# TX_LPF_Add_on.net
KiCad netlist of a schematic drawn in Altium Designer
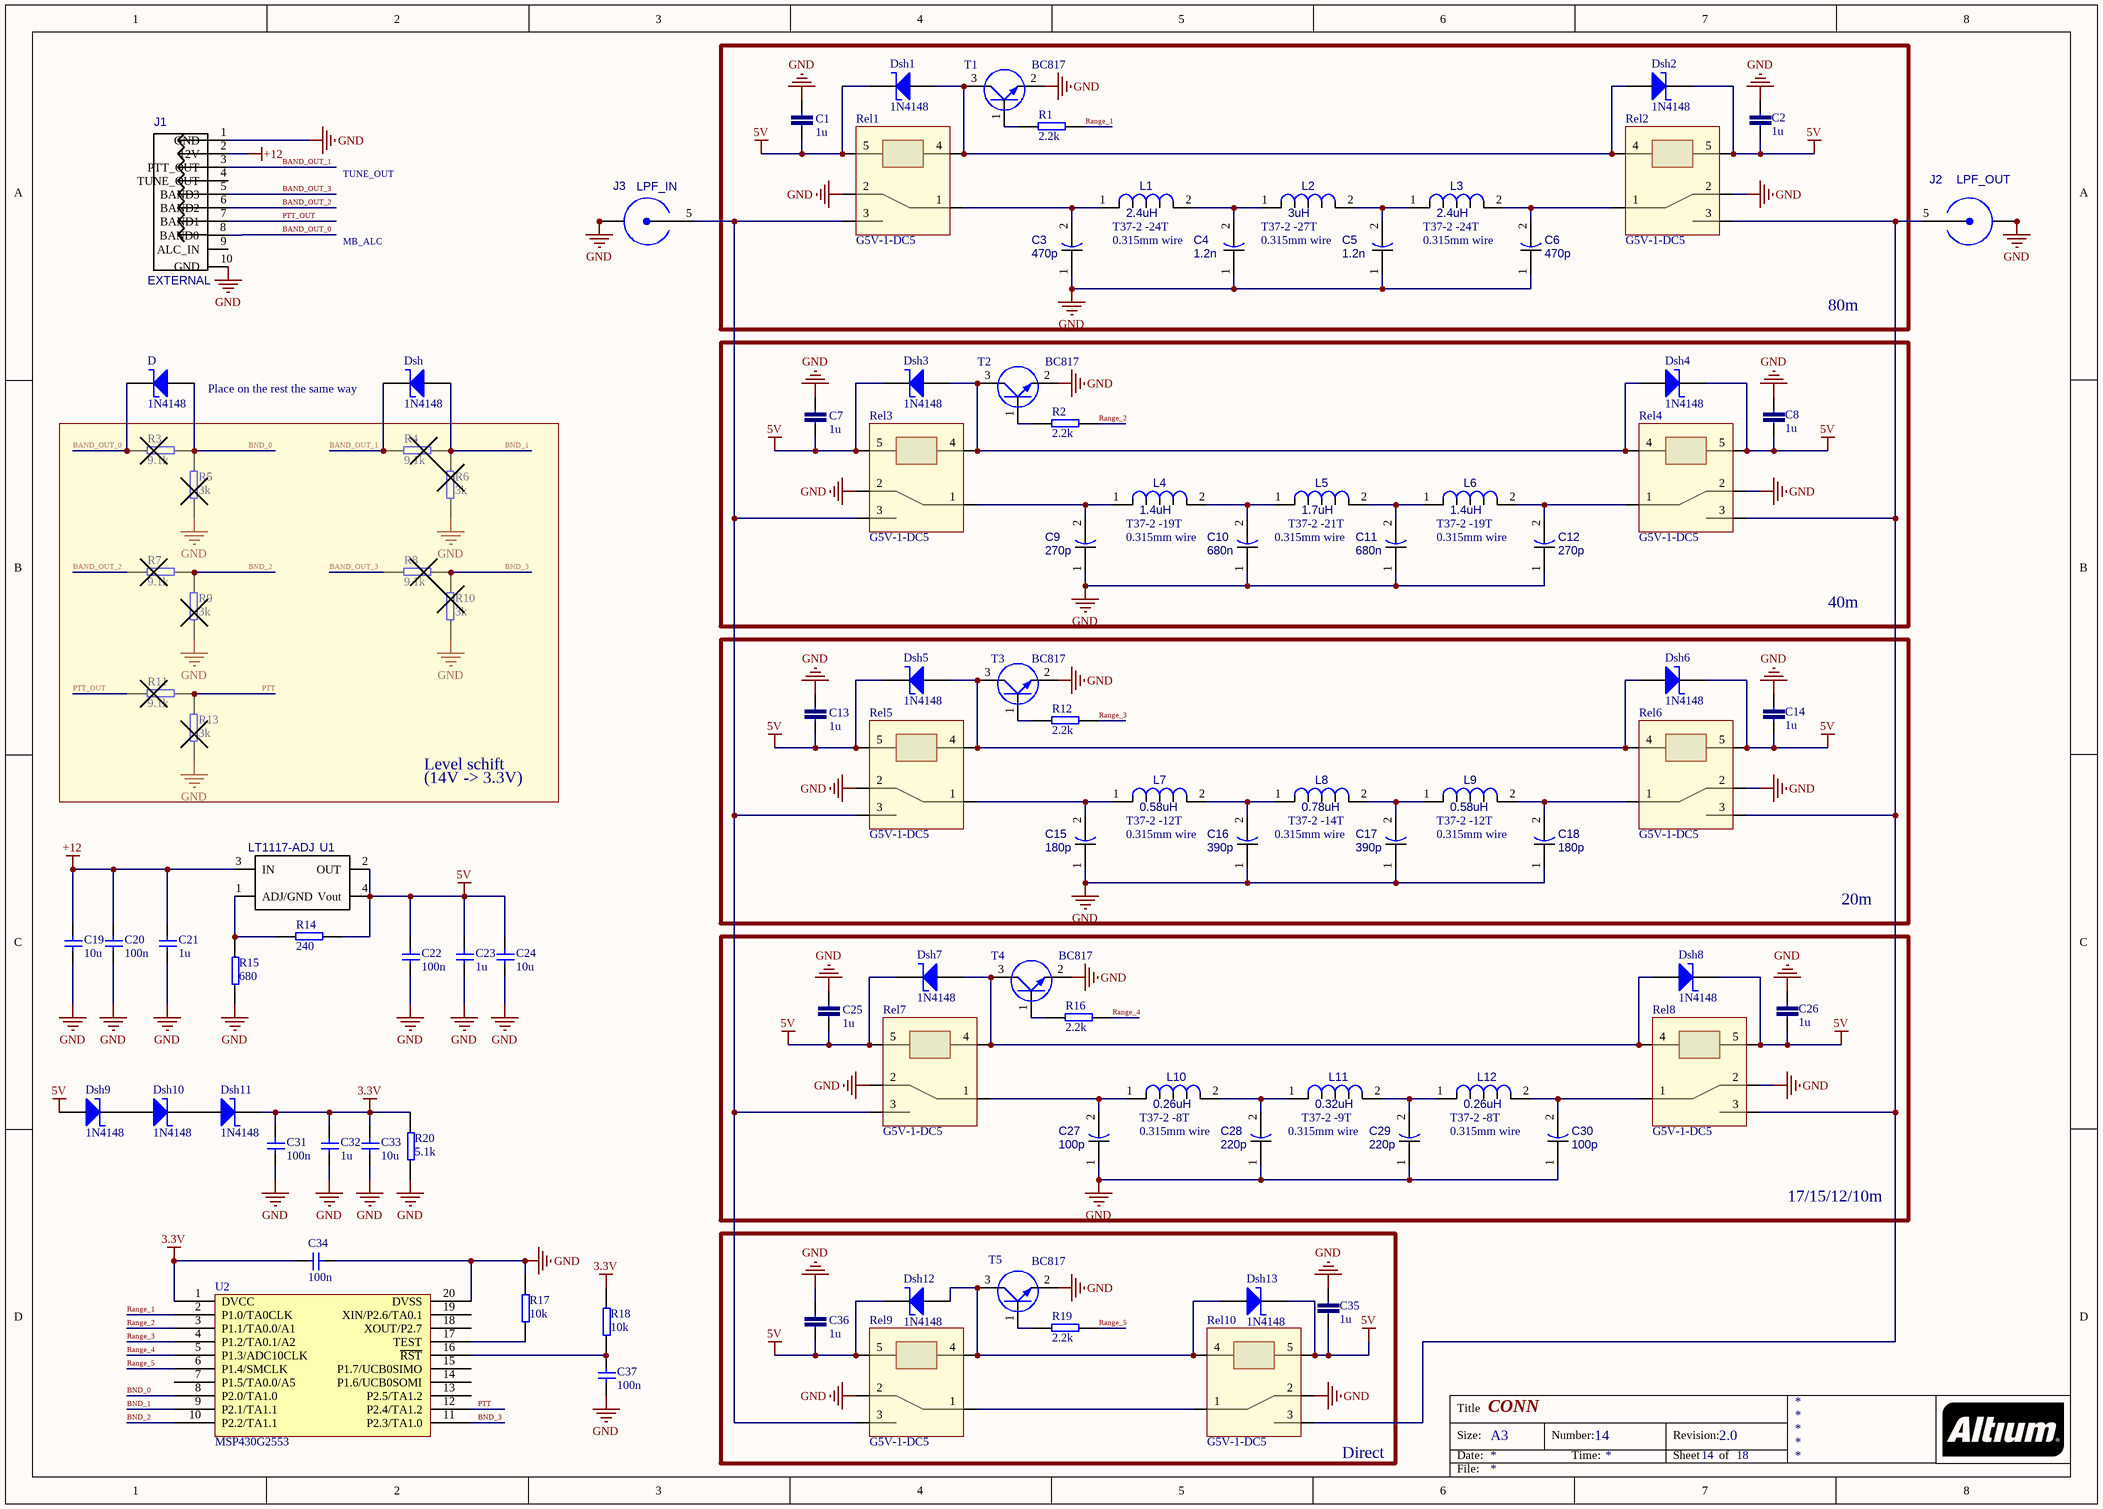
[diagram p0: TX_LPF_Add_on.SchDoc]

(export (version "E")
  (design (tool "Eeschema 10.0.6"))
  (components
    (comp (ref "C1")
      (value "1u")
      (footprint "0805S")
      (description "Capacitor")
      (libsource (lib "XXYZZB_1") (part "C-EUC0805"))
    )
    (comp (ref "C2")
      (value "1u")
      (footprint "0805S")
      (description "Capacitor")
      (libsource (lib "") (part "C-EUC0805_1"))
    )
    (comp (ref "C3")
      (value "470p")
      (footprint "CAP_5mm")
      (description "CAP_1206")
      (fields (field (name "Comment") "CAP_5mm"))
      (libsource (lib "RF-UNIT") (part "CAP_5mm"))
    )
    (comp (ref "C4")
      (value "1.2n")
      (footprint "CAP_5mm")
      (description "CAP_1206")
      (fields (field (name "Comment") "CAP_5mm"))
      (libsource (lib "RF-UNIT") (part "CAP_5mm"))
    )
    (comp (ref "C5")
      (value "1.2n")
      (footprint "CAP_5mm")
      (description "CAP_1206")
      (fields (field (name "Comment") "CAP_5mm"))
      (libsource (lib "RF-UNIT") (part "CAP_5mm"))
    )
    (comp (ref "C6")
      (value "470p")
      (footprint "CAP_5mm")
      (description "CAP_1206")
      (fields (field (name "Comment") "CAP_5mm"))
      (libsource (lib "RF-UNIT") (part "CAP_5mm"))
    )
    (comp (ref "C7")
      (value "1u")
      (footprint "0805S")
      (description "Capacitor")
      (libsource (lib "XXYZZB_1") (part "C-EUC0805"))
    )
    (comp (ref "C8")
      (value "1u")
      (footprint "0805S")
      (description "Capacitor")
      (libsource (lib "") (part "C-EUC0805_1"))
    )
    (comp (ref "C9")
      (value "270p")
      (footprint "CAP_5mm")
      (description "CAP_1206")
      (fields (field (name "Comment") "CAP_5mm"))
      (libsource (lib "RF-UNIT") (part "CAP_5mm"))
    )
    (comp (ref "C10")
      (value "680n")
      (footprint "CAP_5mm")
      (description "CAP_1206")
      (fields (field (name "Comment") "CAP_5mm"))
      (libsource (lib "RF-UNIT") (part "CAP_5mm"))
    )
    (comp (ref "C11")
      (value "680n")
      (footprint "CAP_5mm")
      (description "CAP_1206")
      (fields (field (name "Comment") "CAP_5mm"))
      (libsource (lib "RF-UNIT") (part "CAP_5mm"))
    )
    (comp (ref "C12")
      (value "270p")
      (footprint "CAP_5mm")
      (description "CAP_1206")
      (fields (field (name "Comment") "CAP_5mm"))
      (libsource (lib "RF-UNIT") (part "CAP_5mm"))
    )
    (comp (ref "C13")
      (value "1u")
      (footprint "0805S")
      (description "Capacitor")
      (libsource (lib "XXYZZB_1") (part "C-EUC0805"))
    )
    (comp (ref "C14")
      (value "1u")
      (footprint "0805S")
      (description "Capacitor")
      (libsource (lib "") (part "C-EUC0805_1"))
    )
    (comp (ref "C15")
      (value "180p")
      (footprint "CAP_5mm")
      (description "CAP_1206")
      (fields (field (name "Comment") "CAP_5mm"))
      (libsource (lib "RF-UNIT") (part "CAP_5mm"))
    )
    (comp (ref "C16")
      (value "390p")
      (footprint "CAP_5mm")
      (description "CAP_1206")
      (fields (field (name "Comment") "CAP_5mm"))
      (libsource (lib "RF-UNIT") (part "CAP_5mm"))
    )
    (comp (ref "C17")
      (value "390p")
      (footprint "CAP_5mm")
      (description "CAP_1206")
      (fields (field (name "Comment") "CAP_5mm"))
      (libsource (lib "RF-UNIT") (part "CAP_5mm"))
    )
    (comp (ref "C18")
      (value "180p")
      (footprint "CAP_5mm")
      (description "CAP_1206")
      (fields (field (name "Comment") "CAP_5mm"))
      (libsource (lib "RF-UNIT") (part "CAP_5mm"))
    )
    (comp (ref "C19")
      (value "10u")
      (footprint "CAP_1206")
      (description "Capacitor")
      (fields (field (name "Comment") "C0805"))
      (libsource (lib "Ivan DXP SCH LIB") (part "C0805"))
    )
    (comp (ref "C20")
      (value "100n")
      (footprint "0805S")
      (description "Capacitor")
      (fields (field (name "Comment") "C0805"))
      (libsource (lib "Ivan DXP SCH LIB") (part "C0805"))
    )
    (comp (ref "C21")
      (value "1u")
      (footprint "0805S")
      (description "Capacitor")
      (fields (field (name "Comment") "C0805"))
      (libsource (lib "Ivan DXP SCH LIB") (part "C0805"))
    )
    (comp (ref "C22")
      (value "100n")
      (footprint "0805S")
      (description "Capacitor")
      (fields (field (name "Comment") "C0805"))
      (libsource (lib "Ivan DXP SCH LIB") (part "C0805"))
    )
    (comp (ref "C23")
      (value "1u")
      (footprint "0805S")
      (description "Capacitor")
      (fields (field (name "Comment") "C0805"))
      (libsource (lib "Ivan DXP SCH LIB") (part "C0805"))
    )
    (comp (ref "C24")
      (value "10u")
      (footprint "CAP_1206")
      (description "Capacitor")
      (fields (field (name "Comment") "C0805"))
      (libsource (lib "Ivan DXP SCH LIB") (part "C0805"))
    )
    (comp (ref "C25")
      (value "1u")
      (footprint "0805S")
      (description "Capacitor")
      (libsource (lib "XXYZZB_1") (part "C-EUC0805"))
    )
    (comp (ref "C26")
      (value "1u")
      (footprint "0805S")
      (description "Capacitor")
      (libsource (lib "") (part "C-EUC0805_1"))
    )
    (comp (ref "C27")
      (value "100p")
      (footprint "CAP_5mm")
      (description "CAP_1206")
      (fields (field (name "Comment") "CAP_5mm"))
      (libsource (lib "RF-UNIT") (part "CAP_5mm"))
    )
    (comp (ref "C28")
      (value "220p")
      (footprint "CAP_5mm")
      (description "CAP_1206")
      (fields (field (name "Comment") "CAP_5mm"))
      (libsource (lib "RF-UNIT") (part "CAP_5mm"))
    )
    (comp (ref "C29")
      (value "220p")
      (footprint "CAP_5mm")
      (description "CAP_1206")
      (fields (field (name "Comment") "CAP_5mm"))
      (libsource (lib "RF-UNIT") (part "CAP_5mm"))
    )
    (comp (ref "C30")
      (value "100p")
      (footprint "CAP_5mm")
      (description "CAP_1206")
      (fields (field (name "Comment") "CAP_5mm"))
      (libsource (lib "RF-UNIT") (part "CAP_5mm"))
    )
    (comp (ref "C31")
      (value "100n")
      (footprint "0805S")
      (description "Capacitor")
      (fields (field (name "Comment") "C0805"))
      (libsource (lib "Ivan DXP SCH LIB") (part "C0805"))
    )
    (comp (ref "C32")
      (value "1u")
      (footprint "0805S")
      (description "Capacitor")
      (fields (field (name "Comment") "C0805"))
      (libsource (lib "Ivan DXP SCH LIB") (part "C0805"))
    )
    (comp (ref "C33")
      (value "10u")
      (footprint "CAP_1206")
      (description "Capacitor")
      (fields (field (name "Comment") "C0805"))
      (libsource (lib "Ivan DXP SCH LIB") (part "C0805"))
    )
    (comp (ref "C34")
      (value "100n")
      (footprint "0805S")
      (description "Capacitor")
      (fields (field (name "Comment") "C0805"))
      (libsource (lib "Ivan DXP SCH LIB") (part "C0805"))
    )
    (comp (ref "C35")
      (value "1u")
      (footprint "0805S")
      (description "Capacitor")
      (libsource (lib "") (part "C-EUC0805_1"))
    )
    (comp (ref "C36")
      (value "1u")
      (footprint "0805S")
      (description "Capacitor")
      (libsource (lib "XXYZZB_1") (part "C-EUC0805"))
    )
    (comp (ref "C37")
      (value "100n")
      (footprint "0805S")
      (description "Capacitor")
      (fields (field (name "Comment") "C0805"))
      (libsource (lib "Ivan DXP SCH LIB") (part "C0805"))
    )
    (comp (ref "D")
      (value "1N4148")
      (footprint "1N4148 (1005)")
      (description "Diode Shottky")
      (fields (field (name "Comment") "DIODE_Shottky_Micr.M"))
      (libsource (lib "Ivan DXP SCH LIB") (part "DIODE_Shottky_Micr.M"))
    )
    (comp (ref "Dsh")
      (value "1N4148")
      (footprint "1N4148 (1005)")
      (description "Diode Shottky")
      (fields (field (name "Comment") "DIODE_Shottky_Micr.M"))
      (libsource (lib "Ivan DXP SCH LIB") (part "DIODE_Shottky_Micr.M"))
    )
    (comp (ref "Dsh1")
      (value "1N4148")
      (footprint "1N4148 (1005)")
      (description "Diode Shottky")
      (fields (field (name "Comment") "DIODE_Shottky_Micr.M"))
      (libsource (lib "Ivan DXP SCH LIB") (part "DIODE_Shottky_Micr.M"))
    )
    (comp (ref "Dsh2")
      (value "1N4148")
      (footprint "1N4148 (1005)")
      (description "Diode Shottky")
      (fields (field (name "Comment") "DIODE_Shottky_Micr.M"))
      (libsource (lib "Ivan DXP SCH LIB") (part "DIODE_Shottky_Micr.M"))
    )
    (comp (ref "Dsh3")
      (value "1N4148")
      (footprint "1N4148 (1005)")
      (description "Diode Shottky")
      (fields (field (name "Comment") "DIODE_Shottky_Micr.M"))
      (libsource (lib "Ivan DXP SCH LIB") (part "DIODE_Shottky_Micr.M"))
    )
    (comp (ref "Dsh4")
      (value "1N4148")
      (footprint "1N4148 (1005)")
      (description "Diode Shottky")
      (fields (field (name "Comment") "DIODE_Shottky_Micr.M"))
      (libsource (lib "Ivan DXP SCH LIB") (part "DIODE_Shottky_Micr.M"))
    )
    (comp (ref "Dsh5")
      (value "1N4148")
      (footprint "1N4148 (1005)")
      (description "Diode Shottky")
      (fields (field (name "Comment") "DIODE_Shottky_Micr.M"))
      (libsource (lib "Ivan DXP SCH LIB") (part "DIODE_Shottky_Micr.M"))
    )
    (comp (ref "Dsh6")
      (value "1N4148")
      (footprint "1N4148 (1005)")
      (description "Diode Shottky")
      (fields (field (name "Comment") "DIODE_Shottky_Micr.M"))
      (libsource (lib "Ivan DXP SCH LIB") (part "DIODE_Shottky_Micr.M"))
    )
    (comp (ref "Dsh7")
      (value "1N4148")
      (footprint "1N4148 (1005)")
      (description "Diode Shottky")
      (fields (field (name "Comment") "DIODE_Shottky_Micr.M"))
      (libsource (lib "Ivan DXP SCH LIB") (part "DIODE_Shottky_Micr.M"))
    )
    (comp (ref "Dsh8")
      (value "1N4148")
      (footprint "1N4148 (1005)")
      (description "Diode Shottky")
      (fields (field (name "Comment") "DIODE_Shottky_Micr.M"))
      (libsource (lib "Ivan DXP SCH LIB") (part "DIODE_Shottky_Micr.M"))
    )
    (comp (ref "Dsh9")
      (value "1N4148")
      (footprint "1N4148 (1005)")
      (description "Diode Shottky")
      (fields (field (name "Comment") "DIODE_Shottky_Micr.M"))
      (libsource (lib "Ivan DXP SCH LIB") (part "DIODE_Shottky_Micr.M"))
    )
    (comp (ref "Dsh10")
      (value "1N4148")
      (footprint "1N4148 (1005)")
      (description "Diode Shottky")
      (fields (field (name "Comment") "DIODE_Shottky_Micr.M"))
      (libsource (lib "Ivan DXP SCH LIB") (part "DIODE_Shottky_Micr.M"))
    )
    (comp (ref "Dsh11")
      (value "1N4148")
      (footprint "1N4148 (1005)")
      (description "Diode Shottky")
      (fields (field (name "Comment") "DIODE_Shottky_Micr.M"))
      (libsource (lib "Ivan DXP SCH LIB") (part "DIODE_Shottky_Micr.M"))
    )
    (comp (ref "Dsh12")
      (value "1N4148")
      (footprint "1N4148 (1005)")
      (description "Diode Shottky")
      (fields (field (name "Comment") "DIODE_Shottky_Micr.M"))
      (libsource (lib "Ivan DXP SCH LIB") (part "DIODE_Shottky_Micr.M"))
    )
    (comp (ref "Dsh13")
      (value "1N4148")
      (footprint "1N4148 (1005)")
      (description "Diode Shottky")
      (fields (field (name "Comment") "DIODE_Shottky_Micr.M"))
      (libsource (lib "Ivan DXP SCH LIB") (part "DIODE_Shottky_Micr.M"))
    )
    (comp (ref "J1")
      (value "EXTERNAL")
      (footprint "90131-0126")
      (description "2*5 PIN")
      (libsource (lib "RF-UNIT") (part "90131-0126"))
    )
    (comp (ref "J2")
      (value "LPF_OUT")
      (footprint "31-5431")
      (description "SMA")
      (fields (field (name "Comment") "Output"))
      (libsource (lib "RF-UNIT_1") (part "31-5431"))
    )
    (comp (ref "J3")
      (value "LPF_IN")
      (footprint "31-5431")
      (description "SMA")
      (fields (field (name "Comment") "Input"))
      (libsource (lib "RF-UNIT_1") (part "31-5431"))
    )
    (comp (ref "L1")
      (value "2.4uH")
      (footprint "IND_T37-2")
      (description "IND_T37-2")
      (libsource (lib "RF-UNIT") (part "IND_T37-2"))
    )
    (comp (ref "L2")
      (value "3uH")
      (footprint "IND_T37-2")
      (description "IND_T37-2")
      (libsource (lib "RF-UNIT") (part "IND_T37-2"))
    )
    (comp (ref "L3")
      (value "2.4uH")
      (footprint "IND_T37-2")
      (description "IND_T37-2")
      (libsource (lib "RF-UNIT") (part "IND_T37-2"))
    )
    (comp (ref "L4")
      (value "1.4uH")
      (footprint "IND_T37-2")
      (description "IND_T37-2")
      (libsource (lib "RF-UNIT") (part "IND_T37-2"))
    )
    (comp (ref "L5")
      (value "1.7uH")
      (footprint "IND_T37-2")
      (description "IND_T37-2")
      (libsource (lib "RF-UNIT") (part "IND_T37-2"))
    )
    (comp (ref "L6")
      (value "1.4uH")
      (footprint "IND_T37-2")
      (description "IND_T37-2")
      (libsource (lib "RF-UNIT") (part "IND_T37-2"))
    )
    (comp (ref "L7")
      (value "0.58uH")
      (footprint "IND_T37-2")
      (description "IND_T37-2")
      (libsource (lib "RF-UNIT") (part "IND_T37-2"))
    )
    (comp (ref "L8")
      (value "0.78uH")
      (footprint "IND_T37-2")
      (description "IND_T37-2")
      (libsource (lib "RF-UNIT") (part "IND_T37-2"))
    )
    (comp (ref "L9")
      (value "0.58uH")
      (footprint "IND_T37-2")
      (description "IND_T37-2")
      (libsource (lib "RF-UNIT") (part "IND_T37-2"))
    )
    (comp (ref "L10")
      (value "0.26uH")
      (footprint "IND_T37-2")
      (description "IND_T37-2")
      (libsource (lib "RF-UNIT") (part "IND_T37-2"))
    )
    (comp (ref "L11")
      (value "0.32uH")
      (footprint "IND_T37-2")
      (description "IND_T37-2")
      (libsource (lib "RF-UNIT") (part "IND_T37-2"))
    )
    (comp (ref "L12")
      (value "0.26uH")
      (footprint "IND_T37-2")
      (description "IND_T37-2")
      (libsource (lib "RF-UNIT") (part "IND_T37-2"))
    )
    (comp (ref "R1")
      (value "2.2k")
      (footprint "0805S")
      (description "Resistor")
      (libsource (lib "Ivan DXP SCH LIB") (part "R0805"))
    )
    (comp (ref "R2")
      (value "2.2k")
      (footprint "0805S")
      (description "Resistor")
      (libsource (lib "Ivan DXP SCH LIB") (part "R0805"))
    )
    (comp (ref "R3")
      (value "9.1k")
      (footprint "0805S")
      (description "Resistor")
      (fields (field (name "Comment") "R0805"))
      (libsource (lib "Ivan DXP SCH LIB") (part "R0805"))
    )
    (comp (ref "R4")
      (value "9.1k")
      (footprint "0805S")
      (description "Resistor")
      (fields (field (name "Comment") "R0805"))
      (libsource (lib "Ivan DXP SCH LIB") (part "R0805"))
    )
    (comp (ref "R5")
      (value "3k")
      (footprint "0805S")
      (description "Resistor")
      (fields (field (name "Comment") "R0805"))
      (libsource (lib "") (part "R0805_1"))
    )
    (comp (ref "R6")
      (value "3k")
      (footprint "0805S")
      (description "Resistor")
      (fields (field (name "Comment") "R0805"))
      (libsource (lib "") (part "R0805_1"))
    )
    (comp (ref "R7")
      (value "9.1k")
      (footprint "0805S")
      (description "Resistor")
      (fields (field (name "Comment") "R0805"))
      (libsource (lib "Ivan DXP SCH LIB") (part "R0805"))
    )
    (comp (ref "R8")
      (value "9.1k")
      (footprint "0805S")
      (description "Resistor")
      (fields (field (name "Comment") "R0805"))
      (libsource (lib "Ivan DXP SCH LIB") (part "R0805"))
    )
    (comp (ref "R9")
      (value "3k")
      (footprint "0805S")
      (description "Resistor")
      (fields (field (name "Comment") "R0805"))
      (libsource (lib "") (part "R0805_1"))
    )
    (comp (ref "R10")
      (value "3k")
      (footprint "0805S")
      (description "Resistor")
      (fields (field (name "Comment") "R0805"))
      (libsource (lib "") (part "R0805_1"))
    )
    (comp (ref "R11")
      (value "9.1k")
      (footprint "0805S")
      (description "Resistor")
      (fields (field (name "Comment") "R0805"))
      (libsource (lib "Ivan DXP SCH LIB") (part "R0805"))
    )
    (comp (ref "R12")
      (value "2.2k")
      (footprint "0805S")
      (description "Resistor")
      (libsource (lib "Ivan DXP SCH LIB") (part "R0805"))
    )
    (comp (ref "R13")
      (value "3k")
      (footprint "0805S")
      (description "Resistor")
      (fields (field (name "Comment") "R0805"))
      (libsource (lib "") (part "R0805_1"))
    )
    (comp (ref "R14")
      (value "240")
      (footprint "0805S")
      (description "Resistor")
      (fields (field (name "Comment") "R0805"))
      (libsource (lib "Ivan DXP SCH LIB") (part "R0805"))
    )
    (comp (ref "R15")
      (value "680")
      (footprint "0805S")
      (description "Resistor")
      (fields (field (name "Comment") "R0805"))
      (libsource (lib "") (part "R0805_2"))
    )
    (comp (ref "R16")
      (value "2.2k")
      (footprint "0805S")
      (description "Resistor")
      (libsource (lib "Ivan DXP SCH LIB") (part "R0805"))
    )
    (comp (ref "R17")
      (value "10k")
      (footprint "0805S")
      (description "Resistor")
      (fields (field (name "Comment") "R0805"))
      (libsource (lib "") (part "R0805_2"))
    )
    (comp (ref "R18")
      (value "10k")
      (footprint "0805S")
      (description "Resistor")
      (fields (field (name "Comment") "R0805"))
      (libsource (lib "") (part "R0805_2"))
    )
    (comp (ref "R19")
      (value "2.2k")
      (footprint "0805S")
      (description "Resistor")
      (libsource (lib "Ivan DXP SCH LIB") (part "R0805"))
    )
    (comp (ref "R20")
      (value "5.1k")
      (footprint "0805S")
      (description "Resistor")
      (fields (field (name "Comment") "R0805"))
      (libsource (lib "") (part "R0805_2"))
    )
    (comp (ref "Rel1") (value "G5V-1-DC5") (footprint "G5V-1") (libsource (lib "") (part "G5V-1-DC5_1")))
    (comp (ref "Rel2")
      (value "G5V-1-DC5")
      (footprint "G5V-1")
      (libsource (lib "IC_Texas_Instruments_ADS805E_eec") (part "G5V-1-DC5"))
    )
    (comp (ref "Rel3") (value "G5V-1-DC5") (footprint "G5V-1") (libsource (lib "") (part "G5V-1-DC5_1")))
    (comp (ref "Rel4")
      (value "G5V-1-DC5")
      (footprint "G5V-1")
      (libsource (lib "IC_Texas_Instruments_ADS805E_eec") (part "G5V-1-DC5"))
    )
    (comp (ref "Rel5") (value "G5V-1-DC5") (footprint "G5V-1") (libsource (lib "") (part "G5V-1-DC5_1")))
    (comp (ref "Rel6")
      (value "G5V-1-DC5")
      (footprint "G5V-1")
      (libsource (lib "IC_Texas_Instruments_ADS805E_eec") (part "G5V-1-DC5"))
    )
    (comp (ref "Rel7") (value "G5V-1-DC5") (footprint "G5V-1") (libsource (lib "") (part "G5V-1-DC5_1")))
    (comp (ref "Rel8")
      (value "G5V-1-DC5")
      (footprint "G5V-1")
      (libsource (lib "IC_Texas_Instruments_ADS805E_eec") (part "G5V-1-DC5"))
    )
    (comp (ref "Rel9") (value "G5V-1-DC5") (footprint "G5V-1") (libsource (lib "") (part "G5V-1-DC5_1")))
    (comp (ref "Rel10")
      (value "G5V-1-DC5")
      (footprint "G5V-1")
      (libsource (lib "IC_Texas_Instruments_ADS805E_eec") (part "G5V-1-DC5"))
    )
    (comp (ref "T1")
      (value "BC817")
      (footprint "SOT-23")
      (description "Bipol. Transistor")
      (fields (field (name "Comment") "NPN"))
      (libsource (lib "Ivan DXP SCH LIB") (part "NPN"))
    )
    (comp (ref "T2")
      (value "BC817")
      (footprint "SOT-23")
      (description "Bipol. Transistor")
      (fields (field (name "Comment") "NPN"))
      (libsource (lib "Ivan DXP SCH LIB") (part "NPN"))
    )
    (comp (ref "T3")
      (value "BC817")
      (footprint "SOT-23")
      (description "Bipol. Transistor")
      (fields (field (name "Comment") "NPN"))
      (libsource (lib "Ivan DXP SCH LIB") (part "NPN"))
    )
    (comp (ref "T4")
      (value "BC817")
      (footprint "SOT-23")
      (description "Bipol. Transistor")
      (fields (field (name "Comment") "NPN"))
      (libsource (lib "Ivan DXP SCH LIB") (part "NPN"))
    )
    (comp (ref "T5")
      (value "BC817")
      (footprint "SOT-23")
      (description "Bipol. Transistor")
      (fields (field (name "Comment") "NPN"))
      (libsource (lib "Ivan DXP SCH LIB") (part "NPN"))
    )
    (comp (ref "U1")
      (value "LT1117-ADJ")
      (footprint "LT1117IST-ADJ")
      (description "LT1117IST-ADJ")
      (libsource (lib "*") (part "LT1117IST-ADJ"))
    )
    (comp (ref "U2")
      (value "MSP430G2553")
      (footprint "DIP20M")
      (libsource (lib "Ivan DXP SCH LIB") (part "MSP430G2553"))
    )
  )
  (nets
    (net (code "1") (name "+12") (class "Default")
      (node (ref "C19") (pin "2") (pinfunction "2_2") (pintype "passive"))
      (node (ref "C20") (pin "2") (pinfunction "2_2") (pintype "passive"))
      (node (ref "C21") (pin "2") (pinfunction "2_2") (pintype "passive"))
      (node (ref "J1") (pin "2") (pinfunction "12V_2") (pintype "passive"))
      (node (ref "U1") (pin "3") (pinfunction "IN_3") (pintype "passive"))
    )
    (net (code "3") (name "/BAND_OUT_0") (class "Default")
      (node (ref "D") (pin "K") (pinfunction "K_K") (pintype "passive"))
      (node (ref "J1") (pin "8") (pinfunction "BAND0_8") (pintype "passive"))
      (node (ref "R3") (pin "1") (pinfunction "1_1") (pintype "passive"))
    )
    (net (code "4") (name "/BAND_OUT_1") (class "Default")
      (node (ref "Dsh") (pin "K") (pinfunction "K_K") (pintype "passive"))
      (node (ref "J1") (pin "3") (pinfunction "PTT_OUT_3") (pintype "passive"))
      (node (ref "R4") (pin "1") (pinfunction "1_1") (pintype "passive"))
    )
    (net (code "5") (name "/BAND_OUT_2") (class "Default")
      (node (ref "J1") (pin "6") (pinfunction "BAND2_6") (pintype "passive"))
      (node (ref "R7") (pin "1") (pinfunction "1_1") (pintype "passive"))
    )
    (net (code "6") (name "/BAND_OUT_3") (class "Default")
      (node (ref "J1") (pin "5") (pinfunction "BAND3_5") (pintype "passive"))
      (node (ref "R8") (pin "1") (pinfunction "1_1") (pintype "passive"))
    )
    (net (code "7") (name "/BND_0") (class "Default")
      (node (ref "D") (pin "A") (pinfunction "A_A") (pintype "passive"))
      (node (ref "R3") (pin "2") (pinfunction "2_2") (pintype "passive"))
      (node (ref "R5") (pin "2") (pinfunction "2_2") (pintype "passive"))
      (node (ref "U2") (pin "8") (pinfunction "P2.0/TA1.0_8") (pintype "passive"))
    )
    (net (code "8") (name "/BND_1") (class "Default")
      (node (ref "Dsh") (pin "A") (pinfunction "A_A") (pintype "passive"))
      (node (ref "R4") (pin "2") (pinfunction "2_2") (pintype "passive"))
      (node (ref "R6") (pin "2") (pinfunction "2_2") (pintype "passive"))
      (node (ref "U2") (pin "9") (pinfunction "P2.1/TA1.1_9") (pintype "passive"))
    )
    (net (code "9") (name "/BND_2") (class "Default")
      (node (ref "R7") (pin "2") (pinfunction "2_2") (pintype "passive"))
      (node (ref "R9") (pin "2") (pinfunction "2_2") (pintype "passive"))
      (node (ref "U2") (pin "10") (pinfunction "P2.2/TA1.1_10") (pintype "passive"))
    )
    (net (code "10") (name "/BND_3") (class "Default")
      (node (ref "R10") (pin "2") (pinfunction "2_2") (pintype "passive"))
      (node (ref "R8") (pin "2") (pinfunction "2_2") (pintype "passive"))
      (node (ref "U2") (pin "11") (pinfunction "P2.3/TA1.0_11") (pintype "passive"))
    )
    (net (code "11") (name "/PTT") (class "Default")
      (node (ref "R11") (pin "2") (pinfunction "2_2") (pintype "passive"))
      (node (ref "R13") (pin "2") (pinfunction "2_2") (pintype "passive"))
      (node (ref "U2") (pin "12") (pinfunction "P2.4/TA1.2_12") (pintype "passive"))
    )
    (net (code "12") (name "/PTT_OUT") (class "Default")
      (node (ref "J1") (pin "7") (pinfunction "BAND1_7") (pintype "passive"))
      (node (ref "R11") (pin "1") (pinfunction "1_1") (pintype "passive"))
    )
    (net (code "13") (name "/Range_1") (class "Default")
      (node (ref "R1") (pin "2") (pinfunction "2_2") (pintype "passive"))
      (node (ref "U2") (pin "2") (pinfunction "P1.0/TA0CLK_2") (pintype "passive"))
    )
    (net (code "14") (name "/Range_2") (class "Default")
      (node (ref "R2") (pin "2") (pinfunction "2_2") (pintype "passive"))
      (node (ref "U2") (pin "3") (pinfunction "P1.1/TA0.0/A1_3") (pintype "passive"))
    )
    (net (code "15") (name "/Range_3") (class "Default")
      (node (ref "R12") (pin "2") (pinfunction "2_2") (pintype "passive"))
      (node (ref "U2") (pin "4") (pinfunction "P1.2/TA0.1/A2_4") (pintype "passive"))
    )
    (net (code "16") (name "/Range_4") (class "Default")
      (node (ref "R16") (pin "2") (pinfunction "2_2") (pintype "passive"))
      (node (ref "U2") (pin "5") (pinfunction "P1.3/ADC10CLK_5") (pintype "passive"))
    )
    (net (code "17") (name "/Range_5") (class "Default")
      (node (ref "R19") (pin "2") (pinfunction "2_2") (pintype "passive"))
      (node (ref "U2") (pin "6") (pinfunction "P1.4/SMCLK_6") (pintype "passive"))
    )
    (net (code "18") (name "3.3V") (class "Default")
      (node (ref "C31") (pin "2") (pinfunction "2_2") (pintype "passive"))
      (node (ref "C32") (pin "2") (pinfunction "2_2") (pintype "passive"))
      (node (ref "C33") (pin "2") (pinfunction "2_2") (pintype "passive"))
      (node (ref "C34") (pin "1") (pinfunction "1_1") (pintype "passive"))
      (node (ref "Dsh11") (pin "K") (pinfunction "K_K") (pintype "passive"))
      (node (ref "R18") (pin "1") (pinfunction "1_1") (pintype "passive"))
      (node (ref "R20") (pin "1") (pinfunction "1_1") (pintype "passive"))
      (node (ref "U2") (pin "1") (pinfunction "DVCC_1") (pintype "passive"))
    )
    (net (code "19") (name "5V") (class "Default")
      (node (ref "C1") (pin "1") (pinfunction "1_1") (pintype "passive"))
      (node (ref "C13") (pin "1") (pinfunction "1_1") (pintype "passive"))
      (node (ref "C14") (pin "2") (pinfunction "2_2") (pintype "passive"))
      (node (ref "C2") (pin "2") (pinfunction "2_2") (pintype "passive"))
      (node (ref "C22") (pin "2") (pinfunction "2_2") (pintype "passive"))
      (node (ref "C23") (pin "2") (pinfunction "2_2") (pintype "passive"))
      (node (ref "C24") (pin "2") (pinfunction "2_2") (pintype "passive"))
      (node (ref "C25") (pin "1") (pinfunction "1_1") (pintype "passive"))
      (node (ref "C26") (pin "2") (pinfunction "2_2") (pintype "passive"))
      (node (ref "C35") (pin "2") (pinfunction "2_2") (pintype "passive"))
      (node (ref "C36") (pin "1") (pinfunction "1_1") (pintype "passive"))
      (node (ref "C7") (pin "1") (pinfunction "1_1") (pintype "passive"))
      (node (ref "C8") (pin "2") (pinfunction "2_2") (pintype "passive"))
      (node (ref "Dsh1") (pin "K") (pinfunction "K_K") (pintype "passive"))
      (node (ref "Dsh12") (pin "K") (pinfunction "K_K") (pintype "passive"))
      (node (ref "Dsh13") (pin "K") (pinfunction "K_K") (pintype "passive"))
      (node (ref "Dsh2") (pin "K") (pinfunction "K_K") (pintype "passive"))
      (node (ref "Dsh3") (pin "K") (pinfunction "K_K") (pintype "passive"))
      (node (ref "Dsh4") (pin "K") (pinfunction "K_K") (pintype "passive"))
      (node (ref "Dsh5") (pin "K") (pinfunction "K_K") (pintype "passive"))
      (node (ref "Dsh6") (pin "K") (pinfunction "K_K") (pintype "passive"))
      (node (ref "Dsh7") (pin "K") (pinfunction "K_K") (pintype "passive"))
      (node (ref "Dsh8") (pin "K") (pinfunction "K_K") (pintype "passive"))
      (node (ref "Dsh9") (pin "A") (pinfunction "A_A") (pintype "passive"))
      (node (ref "R14") (pin "2") (pinfunction "2_2") (pintype "passive"))
      (node (ref "Rel1") (pin "5") (pinfunction "5_5") (pintype "passive"))
      (node (ref "Rel10") (pin "5") (pinfunction "5_5") (pintype "passive"))
      (node (ref "Rel2") (pin "5") (pinfunction "5_5") (pintype "passive"))
      (node (ref "Rel3") (pin "5") (pinfunction "5_5") (pintype "passive"))
      (node (ref "Rel4") (pin "5") (pinfunction "5_5") (pintype "passive"))
      (node (ref "Rel5") (pin "5") (pinfunction "5_5") (pintype "passive"))
      (node (ref "Rel6") (pin "5") (pinfunction "5_5") (pintype "passive"))
      (node (ref "Rel7") (pin "5") (pinfunction "5_5") (pintype "passive"))
      (node (ref "Rel8") (pin "5") (pinfunction "5_5") (pintype "passive"))
      (node (ref "Rel9") (pin "5") (pinfunction "5_5") (pintype "passive"))
      (node (ref "U1") (pin "2") (pinfunction "OUT_2") (pintype "passive"))
      (node (ref "U1") (pin "4") (pinfunction "Vout_4") (pintype "passive"))
    )
    (net (code "20") (name "GND") (class "Default")
      (node (ref "C1") (pin "2") (pinfunction "2_2") (pintype "passive"))
      (node (ref "C10") (pin "1") (pinfunction "1_1") (pintype "passive"))
      (node (ref "C11") (pin "1") (pinfunction "1_1") (pintype "passive"))
      (node (ref "C12") (pin "1") (pinfunction "1_1") (pintype "passive"))
      (node (ref "C13") (pin "2") (pinfunction "2_2") (pintype "passive"))
      (node (ref "C14") (pin "1") (pinfunction "1_1") (pintype "passive"))
      (node (ref "C15") (pin "1") (pinfunction "1_1") (pintype "passive"))
      (node (ref "C16") (pin "1") (pinfunction "1_1") (pintype "passive"))
      (node (ref "C17") (pin "1") (pinfunction "1_1") (pintype "passive"))
      (node (ref "C18") (pin "1") (pinfunction "1_1") (pintype "passive"))
      (node (ref "C19") (pin "1") (pinfunction "1_1") (pintype "passive"))
      (node (ref "C2") (pin "1") (pinfunction "1_1") (pintype "passive"))
      (node (ref "C20") (pin "1") (pinfunction "1_1") (pintype "passive"))
      (node (ref "C21") (pin "1") (pinfunction "1_1") (pintype "passive"))
      (node (ref "C22") (pin "1") (pinfunction "1_1") (pintype "passive"))
      (node (ref "C23") (pin "1") (pinfunction "1_1") (pintype "passive"))
      (node (ref "C24") (pin "1") (pinfunction "1_1") (pintype "passive"))
      (node (ref "C25") (pin "2") (pinfunction "2_2") (pintype "passive"))
      (node (ref "C26") (pin "1") (pinfunction "1_1") (pintype "passive"))
      (node (ref "C27") (pin "1") (pinfunction "1_1") (pintype "passive"))
      (node (ref "C28") (pin "1") (pinfunction "1_1") (pintype "passive"))
      (node (ref "C29") (pin "1") (pinfunction "1_1") (pintype "passive"))
      (node (ref "C3") (pin "1") (pinfunction "1_1") (pintype "passive"))
      (node (ref "C30") (pin "1") (pinfunction "1_1") (pintype "passive"))
      (node (ref "C31") (pin "1") (pinfunction "1_1") (pintype "passive"))
      (node (ref "C32") (pin "1") (pinfunction "1_1") (pintype "passive"))
      (node (ref "C33") (pin "1") (pinfunction "1_1") (pintype "passive"))
      (node (ref "C34") (pin "2") (pinfunction "2_2") (pintype "passive"))
      (node (ref "C35") (pin "1") (pinfunction "1_1") (pintype "passive"))
      (node (ref "C36") (pin "2") (pinfunction "2_2") (pintype "passive"))
      (node (ref "C37") (pin "1") (pinfunction "1_1") (pintype "passive"))
      (node (ref "C4") (pin "1") (pinfunction "1_1") (pintype "passive"))
      (node (ref "C5") (pin "1") (pinfunction "1_1") (pintype "passive"))
      (node (ref "C6") (pin "1") (pinfunction "1_1") (pintype "passive"))
      (node (ref "C7") (pin "2") (pinfunction "2_2") (pintype "passive"))
      (node (ref "C8") (pin "1") (pinfunction "1_1") (pintype "passive"))
      (node (ref "C9") (pin "1") (pinfunction "1_1") (pintype "passive"))
      (node (ref "J1") (pin "1") (pinfunction "GND_1") (pintype "passive"))
      (node (ref "J1") (pin "10") (pinfunction "GND_10") (pintype "passive"))
      (node (ref "J2") (pin "1") (pinfunction "GND_1") (pintype "passive"))
      (node (ref "J2") (pin "2") (pinfunction "GND_2") (pintype "passive"))
      (node (ref "J2") (pin "3") (pinfunction "GND_3") (pintype "passive"))
      (node (ref "J2") (pin "4") (pinfunction "GND_4") (pintype "passive"))
      (node (ref "J3") (pin "1") (pinfunction "GND_1") (pintype "passive"))
      (node (ref "J3") (pin "2") (pinfunction "GND_2") (pintype "passive"))
      (node (ref "J3") (pin "3") (pinfunction "GND_3") (pintype "passive"))
      (node (ref "J3") (pin "4") (pinfunction "GND_4") (pintype "passive"))
      (node (ref "R10") (pin "1") (pinfunction "1_1") (pintype "passive"))
      (node (ref "R13") (pin "1") (pinfunction "1_1") (pintype "passive"))
      (node (ref "R15") (pin "2") (pinfunction "2_2") (pintype "passive"))
      (node (ref "R17") (pin "1") (pinfunction "1_1") (pintype "passive"))
      (node (ref "R20") (pin "2") (pinfunction "2_2") (pintype "passive"))
      (node (ref "R5") (pin "1") (pinfunction "1_1") (pintype "passive"))
      (node (ref "R6") (pin "1") (pinfunction "1_1") (pintype "passive"))
      (node (ref "R9") (pin "1") (pinfunction "1_1") (pintype "passive"))
      (node (ref "Rel1") (pin "2") (pinfunction "2_2") (pintype "passive"))
      (node (ref "Rel10") (pin "2") (pinfunction "2_2") (pintype "passive"))
      (node (ref "Rel2") (pin "2") (pinfunction "2_2") (pintype "passive"))
      (node (ref "Rel3") (pin "2") (pinfunction "2_2") (pintype "passive"))
      (node (ref "Rel4") (pin "2") (pinfunction "2_2") (pintype "passive"))
      (node (ref "Rel5") (pin "2") (pinfunction "2_2") (pintype "passive"))
      (node (ref "Rel6") (pin "2") (pinfunction "2_2") (pintype "passive"))
      (node (ref "Rel7") (pin "2") (pinfunction "2_2") (pintype "passive"))
      (node (ref "Rel8") (pin "2") (pinfunction "2_2") (pintype "passive"))
      (node (ref "Rel9") (pin "2") (pinfunction "2_2") (pintype "passive"))
      (node (ref "T1") (pin "2") (pinfunction "2_2") (pintype "passive"))
      (node (ref "T2") (pin "2") (pinfunction "2_2") (pintype "passive"))
      (node (ref "T3") (pin "2") (pinfunction "2_2") (pintype "passive"))
      (node (ref "T4") (pin "2") (pinfunction "2_2") (pintype "passive"))
      (node (ref "T5") (pin "2") (pinfunction "2_2") (pintype "passive"))
      (node (ref "U2") (pin "20") (pinfunction "DVSS_20") (pintype "passive"))
    )
    (net (code "21") (name "Net-(C3-Pad2)") (class "Default")
      (node (ref "C3") (pin "2") (pinfunction "2_2") (pintype "passive"))
      (node (ref "L1") (pin "1") (pinfunction "1_1") (pintype "passive"))
      (node (ref "Rel1") (pin "1") (pinfunction "1_1") (pintype "passive"))
    )
    (net (code "22") (name "Net-(C4-Pad2)") (class "Default")
      (node (ref "C4") (pin "2") (pinfunction "2_2") (pintype "passive"))
      (node (ref "L1") (pin "2") (pinfunction "2_2") (pintype "passive"))
      (node (ref "L2") (pin "1") (pinfunction "1_1") (pintype "passive"))
    )
    (net (code "23") (name "Net-(C5-Pad2)") (class "Default")
      (node (ref "C5") (pin "2") (pinfunction "2_2") (pintype "passive"))
      (node (ref "L2") (pin "2") (pinfunction "2_2") (pintype "passive"))
      (node (ref "L3") (pin "1") (pinfunction "1_1") (pintype "passive"))
    )
    (net (code "24") (name "Net-(C6-Pad2)") (class "Default")
      (node (ref "C6") (pin "2") (pinfunction "2_2") (pintype "passive"))
      (node (ref "L3") (pin "2") (pinfunction "2_2") (pintype "passive"))
      (node (ref "Rel2") (pin "1") (pinfunction "1_1") (pintype "passive"))
    )
    (net (code "25") (name "Net-(C9-Pad2)") (class "Default")
      (node (ref "C9") (pin "2") (pinfunction "2_2") (pintype "passive"))
      (node (ref "L4") (pin "1") (pinfunction "1_1") (pintype "passive"))
      (node (ref "Rel3") (pin "1") (pinfunction "1_1") (pintype "passive"))
    )
    (net (code "26") (name "Net-(C10-Pad2)") (class "Default")
      (node (ref "C10") (pin "2") (pinfunction "2_2") (pintype "passive"))
      (node (ref "L4") (pin "2") (pinfunction "2_2") (pintype "passive"))
      (node (ref "L5") (pin "1") (pinfunction "1_1") (pintype "passive"))
    )
    (net (code "27") (name "Net-(C11-Pad2)") (class "Default")
      (node (ref "C11") (pin "2") (pinfunction "2_2") (pintype "passive"))
      (node (ref "L5") (pin "2") (pinfunction "2_2") (pintype "passive"))
      (node (ref "L6") (pin "1") (pinfunction "1_1") (pintype "passive"))
    )
    (net (code "28") (name "Net-(C12-Pad2)") (class "Default")
      (node (ref "C12") (pin "2") (pinfunction "2_2") (pintype "passive"))
      (node (ref "L6") (pin "2") (pinfunction "2_2") (pintype "passive"))
      (node (ref "Rel4") (pin "1") (pinfunction "1_1") (pintype "passive"))
    )
    (net (code "29") (name "Net-(C15-Pad2)") (class "Default")
      (node (ref "C15") (pin "2") (pinfunction "2_2") (pintype "passive"))
      (node (ref "L7") (pin "1") (pinfunction "1_1") (pintype "passive"))
      (node (ref "Rel5") (pin "1") (pinfunction "1_1") (pintype "passive"))
    )
    (net (code "30") (name "Net-(C16-Pad2)") (class "Default")
      (node (ref "C16") (pin "2") (pinfunction "2_2") (pintype "passive"))
      (node (ref "L7") (pin "2") (pinfunction "2_2") (pintype "passive"))
      (node (ref "L8") (pin "1") (pinfunction "1_1") (pintype "passive"))
    )
    (net (code "31") (name "Net-(C17-Pad2)") (class "Default")
      (node (ref "C17") (pin "2") (pinfunction "2_2") (pintype "passive"))
      (node (ref "L8") (pin "2") (pinfunction "2_2") (pintype "passive"))
      (node (ref "L9") (pin "1") (pinfunction "1_1") (pintype "passive"))
    )
    (net (code "32") (name "Net-(C18-Pad2)") (class "Default")
      (node (ref "C18") (pin "2") (pinfunction "2_2") (pintype "passive"))
      (node (ref "L9") (pin "2") (pinfunction "2_2") (pintype "passive"))
      (node (ref "Rel6") (pin "1") (pinfunction "1_1") (pintype "passive"))
    )
    (net (code "33") (name "Net-(C27-Pad2)") (class "Default")
      (node (ref "C27") (pin "2") (pinfunction "2_2") (pintype "passive"))
      (node (ref "L10") (pin "1") (pinfunction "1_1") (pintype "passive"))
      (node (ref "Rel7") (pin "1") (pinfunction "1_1") (pintype "passive"))
    )
    (net (code "34") (name "Net-(C28-Pad2)") (class "Default")
      (node (ref "C28") (pin "2") (pinfunction "2_2") (pintype "passive"))
      (node (ref "L10") (pin "2") (pinfunction "2_2") (pintype "passive"))
      (node (ref "L11") (pin "1") (pinfunction "1_1") (pintype "passive"))
    )
    (net (code "35") (name "Net-(C29-Pad2)") (class "Default")
      (node (ref "C29") (pin "2") (pinfunction "2_2") (pintype "passive"))
      (node (ref "L11") (pin "2") (pinfunction "2_2") (pintype "passive"))
      (node (ref "L12") (pin "1") (pinfunction "1_1") (pintype "passive"))
    )
    (net (code "36") (name "Net-(C30-Pad2)") (class "Default")
      (node (ref "C30") (pin "2") (pinfunction "2_2") (pintype "passive"))
      (node (ref "L12") (pin "2") (pinfunction "2_2") (pintype "passive"))
      (node (ref "Rel8") (pin "1") (pinfunction "1_1") (pintype "passive"))
    )
    (net (code "37") (name "Net-(Dsh1-PadA)") (class "Default")
      (node (ref "Dsh1") (pin "A") (pinfunction "A_A") (pintype "passive"))
      (node (ref "Dsh2") (pin "A") (pinfunction "A_A") (pintype "passive"))
      (node (ref "Rel1") (pin "4") (pinfunction "4_4") (pintype "passive"))
      (node (ref "Rel2") (pin "4") (pinfunction "4_4") (pintype "passive"))
      (node (ref "T1") (pin "3") (pinfunction "3_3") (pintype "passive"))
    )
    (net (code "38") (name "Net-(Dsh3-PadA)") (class "Default")
      (node (ref "Dsh3") (pin "A") (pinfunction "A_A") (pintype "passive"))
      (node (ref "Dsh4") (pin "A") (pinfunction "A_A") (pintype "passive"))
      (node (ref "Rel3") (pin "4") (pinfunction "4_4") (pintype "passive"))
      (node (ref "Rel4") (pin "4") (pinfunction "4_4") (pintype "passive"))
      (node (ref "T2") (pin "3") (pinfunction "3_3") (pintype "passive"))
    )
    (net (code "39") (name "Net-(Dsh5-PadA)") (class "Default")
      (node (ref "Dsh5") (pin "A") (pinfunction "A_A") (pintype "passive"))
      (node (ref "Dsh6") (pin "A") (pinfunction "A_A") (pintype "passive"))
      (node (ref "Rel5") (pin "4") (pinfunction "4_4") (pintype "passive"))
      (node (ref "Rel6") (pin "4") (pinfunction "4_4") (pintype "passive"))
      (node (ref "T3") (pin "3") (pinfunction "3_3") (pintype "passive"))
    )
    (net (code "40") (name "Net-(Dsh7-PadA)") (class "Default")
      (node (ref "Dsh7") (pin "A") (pinfunction "A_A") (pintype "passive"))
      (node (ref "Dsh8") (pin "A") (pinfunction "A_A") (pintype "passive"))
      (node (ref "Rel7") (pin "4") (pinfunction "4_4") (pintype "passive"))
      (node (ref "Rel8") (pin "4") (pinfunction "4_4") (pintype "passive"))
      (node (ref "T4") (pin "3") (pinfunction "3_3") (pintype "passive"))
    )
    (net (code "41") (name "Net-(Dsh10-PadA)") (class "Default")
      (node (ref "Dsh10") (pin "A") (pinfunction "A_A") (pintype "passive"))
      (node (ref "Dsh9") (pin "K") (pinfunction "K_K") (pintype "passive"))
    )
    (net (code "42") (name "Net-(Dsh10-PadK)") (class "Default")
      (node (ref "Dsh10") (pin "K") (pinfunction "K_K") (pintype "passive"))
      (node (ref "Dsh11") (pin "A") (pinfunction "A_A") (pintype "passive"))
    )
    (net (code "43") (name "Net-(Dsh12-PadA)") (class "Default")
      (node (ref "Dsh12") (pin "A") (pinfunction "A_A") (pintype "passive"))
      (node (ref "Dsh13") (pin "A") (pinfunction "A_A") (pintype "passive"))
      (node (ref "Rel10") (pin "4") (pinfunction "4_4") (pintype "passive"))
      (node (ref "Rel9") (pin "4") (pinfunction "4_4") (pintype "passive"))
      (node (ref "T5") (pin "3") (pinfunction "3_3") (pintype "passive"))
    )
    (net (code "44") (name "Net-(J2-CON)") (class "Default")
      (node (ref "J2") (pin "5") (pinfunction "CON_5") (pintype "passive"))
      (node (ref "Rel10") (pin "3") (pinfunction "3_3") (pintype "passive"))
      (node (ref "Rel2") (pin "3") (pinfunction "3_3") (pintype "passive"))
      (node (ref "Rel4") (pin "3") (pinfunction "3_3") (pintype "passive"))
      (node (ref "Rel6") (pin "3") (pinfunction "3_3") (pintype "passive"))
      (node (ref "Rel8") (pin "3") (pinfunction "3_3") (pintype "passive"))
    )
    (net (code "45") (name "Net-(J3-CON)") (class "Default")
      (node (ref "J3") (pin "5") (pinfunction "CON_5") (pintype "passive"))
      (node (ref "Rel1") (pin "3") (pinfunction "3_3") (pintype "passive"))
      (node (ref "Rel3") (pin "3") (pinfunction "3_3") (pintype "passive"))
      (node (ref "Rel5") (pin "3") (pinfunction "3_3") (pintype "passive"))
      (node (ref "Rel7") (pin "3") (pinfunction "3_3") (pintype "passive"))
      (node (ref "Rel9") (pin "3") (pinfunction "3_3") (pintype "passive"))
    )
    (net (code "46") (name "Net-(R1-Pad1)") (class "Default")
      (node (ref "R1") (pin "1") (pinfunction "1_1") (pintype "passive"))
      (node (ref "T1") (pin "1") (pinfunction "1_1") (pintype "passive"))
    )
    (net (code "47") (name "Net-(R2-Pad1)") (class "Default")
      (node (ref "R2") (pin "1") (pinfunction "1_1") (pintype "passive"))
      (node (ref "T2") (pin "1") (pinfunction "1_1") (pintype "passive"))
    )
    (net (code "48") (name "Net-(R12-Pad1)") (class "Default")
      (node (ref "R12") (pin "1") (pinfunction "1_1") (pintype "passive"))
      (node (ref "T3") (pin "1") (pinfunction "1_1") (pintype "passive"))
    )
    (net (code "49") (name "Net-(R16-Pad1)") (class "Default")
      (node (ref "R16") (pin "1") (pinfunction "1_1") (pintype "passive"))
      (node (ref "T4") (pin "1") (pinfunction "1_1") (pintype "passive"))
    )
    (net (code "50") (name "Net-(R19-Pad1)") (class "Default")
      (node (ref "R19") (pin "1") (pinfunction "1_1") (pintype "passive"))
      (node (ref "T5") (pin "1") (pinfunction "1_1") (pintype "passive"))
    )
    (net (code "51") (name "Net-(Rel10-Pad1)") (class "Default")
      (node (ref "Rel10") (pin "1") (pinfunction "1_1") (pintype "passive"))
      (node (ref "Rel9") (pin "1") (pinfunction "1_1") (pintype "passive"))
    )
    (net (code "52") (name "Net-(U1-ADJ{slash}GND)") (class "Default")
      (node (ref "R14") (pin "1") (pinfunction "1_1") (pintype "passive"))
      (node (ref "R15") (pin "1") (pinfunction "1_1") (pintype "passive"))
      (node (ref "U1") (pin "1") (pinfunction "ADJ/GND_1") (pintype "passive"))
    )
    (net (code "53") (name "Net-(U2-TEST)") (class "Default")
      (node (ref "R17") (pin "2") (pinfunction "2_2") (pintype "passive"))
      (node (ref "U2") (pin "17") (pinfunction "TEST_17") (pintype "passive"))
    )
    (net (code "54") (name "Net-(U2-~{RST})") (class "Default")
      (node (ref "C37") (pin "2") (pinfunction "2_2") (pintype "passive"))
      (node (ref "R18") (pin "2") (pinfunction "2_2") (pintype "passive"))
      (node (ref "U2") (pin "16") (pinfunction "~{RST}_16") (pintype "passive"))
    )
    (net (code "55") (name "unconnected-(J1-ALC_IN-Pad9)") (class "Default")
      (node (ref "J1") (pin "9") (pinfunction "ALC_IN_9") (pintype "passive"))
    )
    (net (code "56") (name "unconnected-(J1-TUNE_OUT-Pad4)") (class "Default")
      (node (ref "J1") (pin "4") (pinfunction "TUNE_OUT_4") (pintype "passive"))
    )
    (net (code "57") (name "unconnected-(U2-P1.5{slash}TA0.0{slash}A5-Pad7)") (class "Default")
      (node (ref "U2") (pin "7") (pinfunction "P1.5/TA0.0/A5_7") (pintype "passive"))
    )
    (net (code "58") (name "unconnected-(U2-P1.6{slash}UCB0SOMI-Pad14)") (class "Default")
      (node (ref "U2") (pin "14") (pinfunction "P1.6/UCB0SOMI_14") (pintype "passive"))
    )
    (net (code "59") (name "unconnected-(U2-P1.7{slash}UCB0SIMO-Pad15)") (class "Default")
      (node (ref "U2") (pin "15") (pinfunction "P1.7/UCB0SIMO_15") (pintype "passive"))
    )
    (net (code "60") (name "unconnected-(U2-P2.5{slash}TA1.2-Pad13)") (class "Default")
      (node (ref "U2") (pin "13") (pinfunction "P2.5/TA1.2_13") (pintype "passive"))
    )
    (net (code "61") (name "unconnected-(U2-XIN{slash}P2.6{slash}TA0.1-Pad19)") (class "Default")
      (node (ref "U2") (pin "19") (pinfunction "XIN/P2.6/TA0.1_19") (pintype "passive"))
    )
    (net (code "62") (name "unconnected-(U2-XOUT{slash}P2.7-Pad18)") (class "Default")
      (node (ref "U2") (pin "18") (pinfunction "XOUT/P2.7_18") (pintype "passive"))
    )
  )
)
